# LM317T_Var_Sup.net
KiCad netlist of a schematic drawn in EAGLE
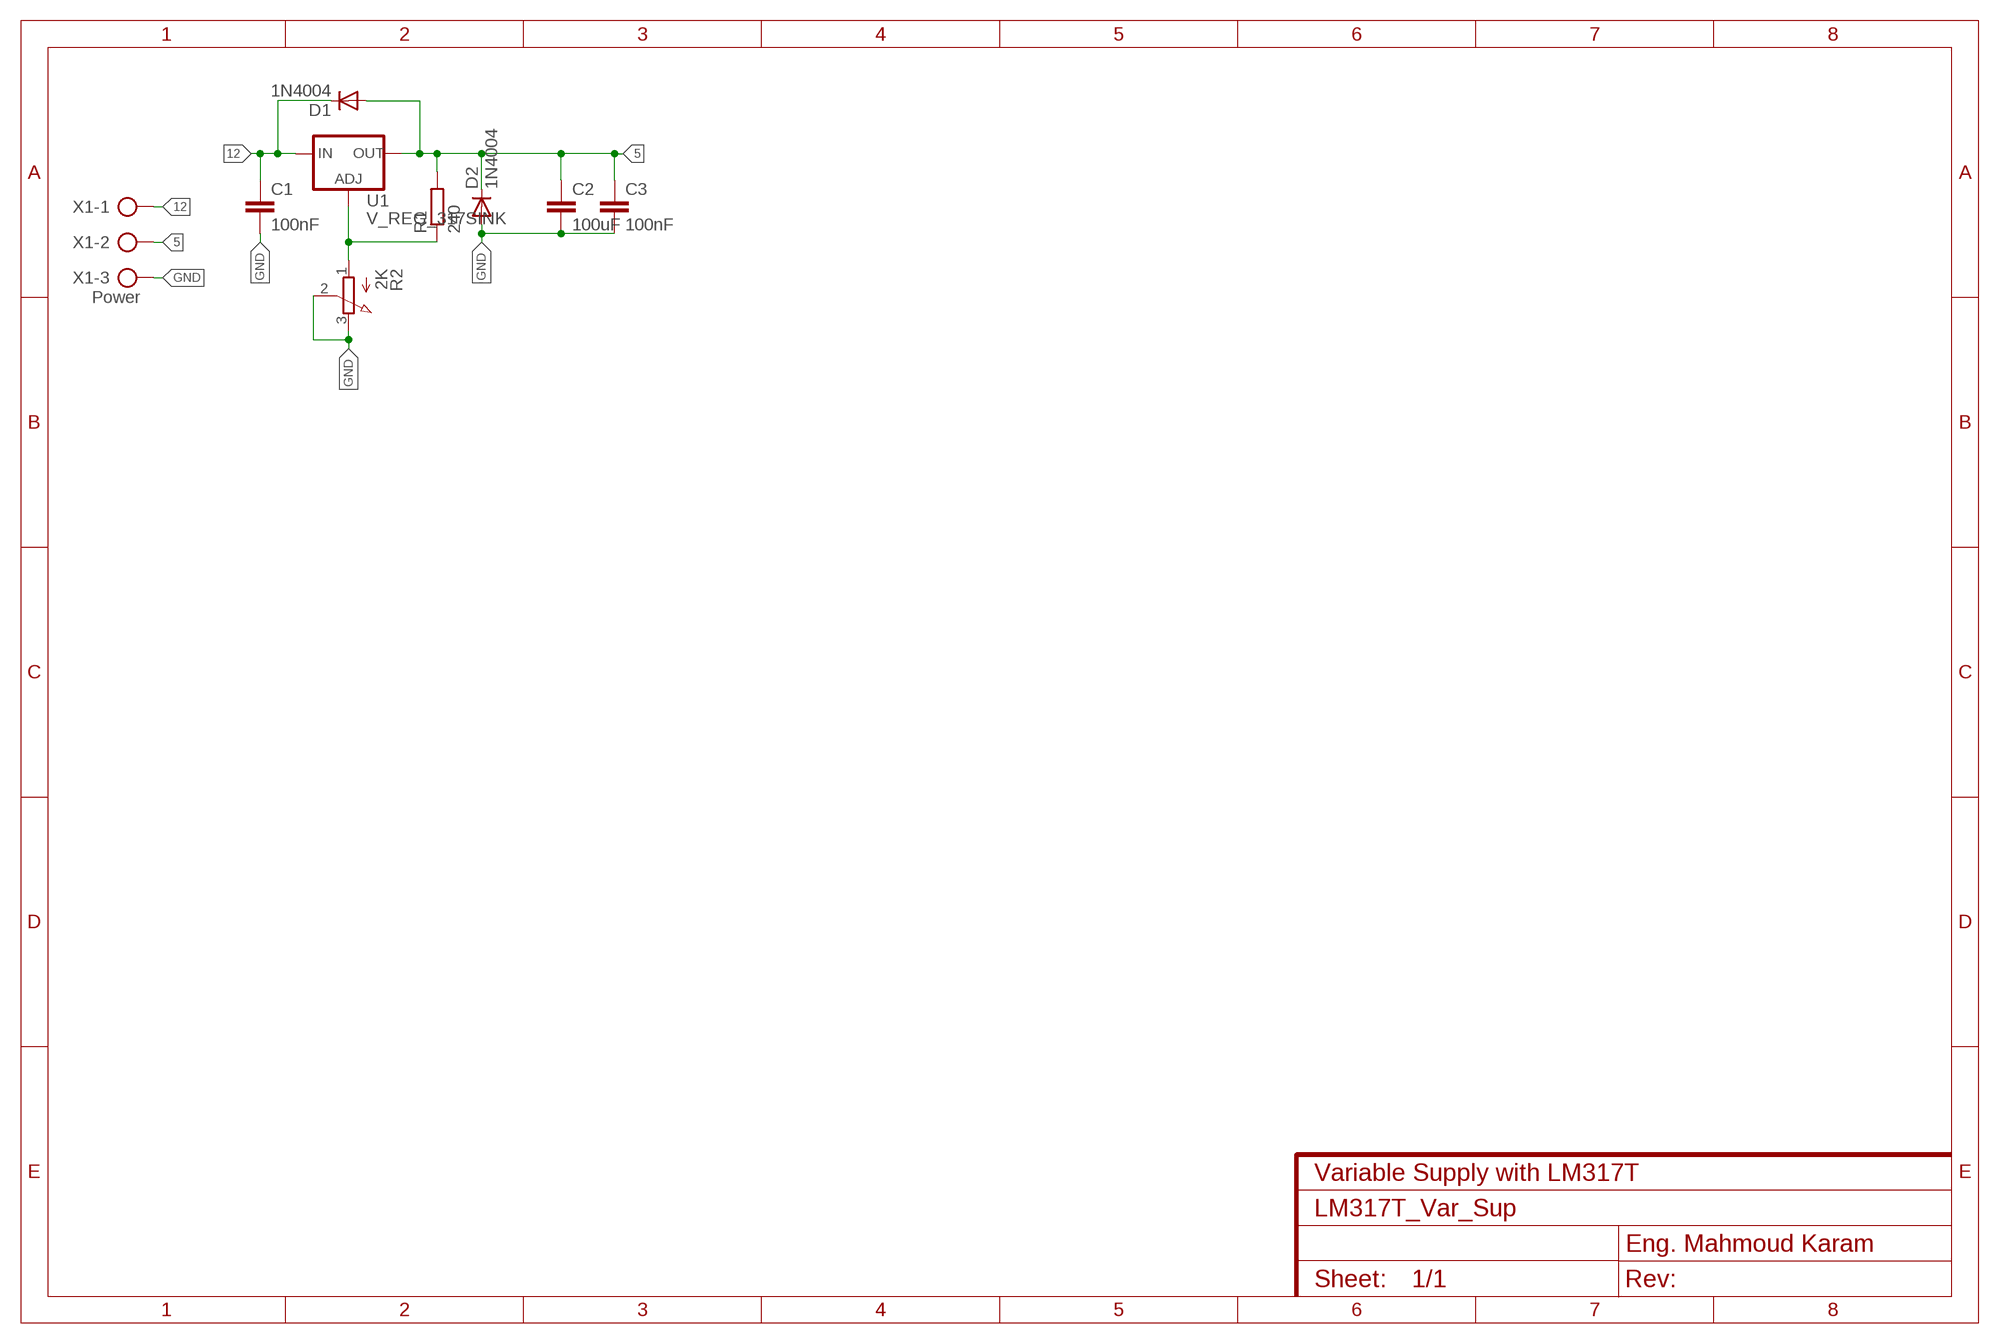
[diagram p0: schematic, sheet 1]

(export (version "E")
  (design (tool "Eeschema 10.0.6"))
  (components
    (comp (ref "C1")
      (value "100nF")
      (footprint "eagle-import:C2.5-2")
      (libsource (lib "eagle-import") (part "C2.5/2"))
    )
    (comp (ref "C2")
      (value "100uF")
      (footprint "eagle-import:C5B5")
      (libsource (lib "eagle-import") (part "C5/5"))
    )
    (comp (ref "C3")
      (value "100nF")
      (footprint "eagle-import:C2.5-2")
      (libsource (lib "eagle-import") (part "C2.5/2"))
    )
    (comp (ref "D1")
      (value "1N4004")
      (footprint "eagle-import:DO41-10")
      (libsource (lib "eagle-import") (part "1N4004"))
    )
    (comp (ref "D2")
      (value "1N4004")
      (footprint "eagle-import:DO41-10")
      (libsource (lib "eagle-import") (part "1N4004"))
    )
    (comp (ref "R1")
      (value "240")
      (footprint "eagle-import:0207_7")
      (libsource (lib "eagle-import") (part "R-EU_0207/7"))
    )
    (comp (ref "R2")
      (value "2K")
      (footprint "eagle-import:3RP_1610N")
      (libsource (lib "eagle-import") (part "3RP/1610N"))
    )
    (comp (ref "U1")
      (value "V_REG_317SINK")
      (footprint "eagle-import:TO220-ADJ")
      (libsource (lib "eagle-import") (part "V_REG_317SINK"))
    )
    (comp (ref "X1")
      (value "Power")
      (footprint "eagle-import:AK500_3-H")
      (libsource (lib "eagle-import") (part "AK500/3-H"))
    )
  )
  (nets
    (net (code "1") (name "5") (class "Default")
      (node (ref "C2") (pin "1") (pinfunction "1_1") (pintype "passive"))
      (node (ref "C3") (pin "1") (pinfunction "1_1") (pintype "passive"))
      (node (ref "D1") (pin "A") (pinfunction "A_A") (pintype "passive"))
      (node (ref "D2") (pin "C") (pinfunction "C_C") (pintype "passive"))
      (node (ref "R1") (pin "2") (pinfunction "2_2") (pintype "passive"))
      (node (ref "U1") (pin "OUT") (pinfunction "OUT_OUT") (pintype "output"))
      (node (ref "X1") (pin "2") (pinfunction "KL_2") (pintype "passive"))
    )
    (net (code "2") (name "12") (class "Default")
      (node (ref "C1") (pin "1") (pinfunction "1_1") (pintype "passive"))
      (node (ref "D1") (pin "C") (pinfunction "C_C") (pintype "passive"))
      (node (ref "U1") (pin "IN") (pinfunction "IN_IN") (pintype "input"))
      (node (ref "X1") (pin "1") (pinfunction "KL_1") (pintype "passive"))
    )
    (net (code "3") (name "GND") (class "Default")
      (node (ref "C1") (pin "2") (pinfunction "2_2") (pintype "passive"))
      (node (ref "C2") (pin "2") (pinfunction "2_2") (pintype "passive"))
      (node (ref "C3") (pin "2") (pinfunction "2_2") (pintype "passive"))
      (node (ref "D2") (pin "A") (pinfunction "A_A") (pintype "passive"))
      (node (ref "R2") (pin "2") (pinfunction "S_2") (pintype "passive"))
      (node (ref "R2") (pin "3") (pinfunction "E_3") (pintype "passive"))
      (node (ref "X1") (pin "3") (pinfunction "KL_3") (pintype "passive"))
    )
    (net (code "4") (name "Net-(R2-A)") (class "Default")
      (node (ref "R1") (pin "1") (pinfunction "1_1") (pintype "passive"))
      (node (ref "R2") (pin "1") (pinfunction "A_1") (pintype "passive"))
      (node (ref "U1") (pin "ADJ") (pinfunction "ADJ_ADJ") (pintype "input"))
    )
  )
)
